# matrix.net
KiCad netlist of a schematic drawn in Altium Designer
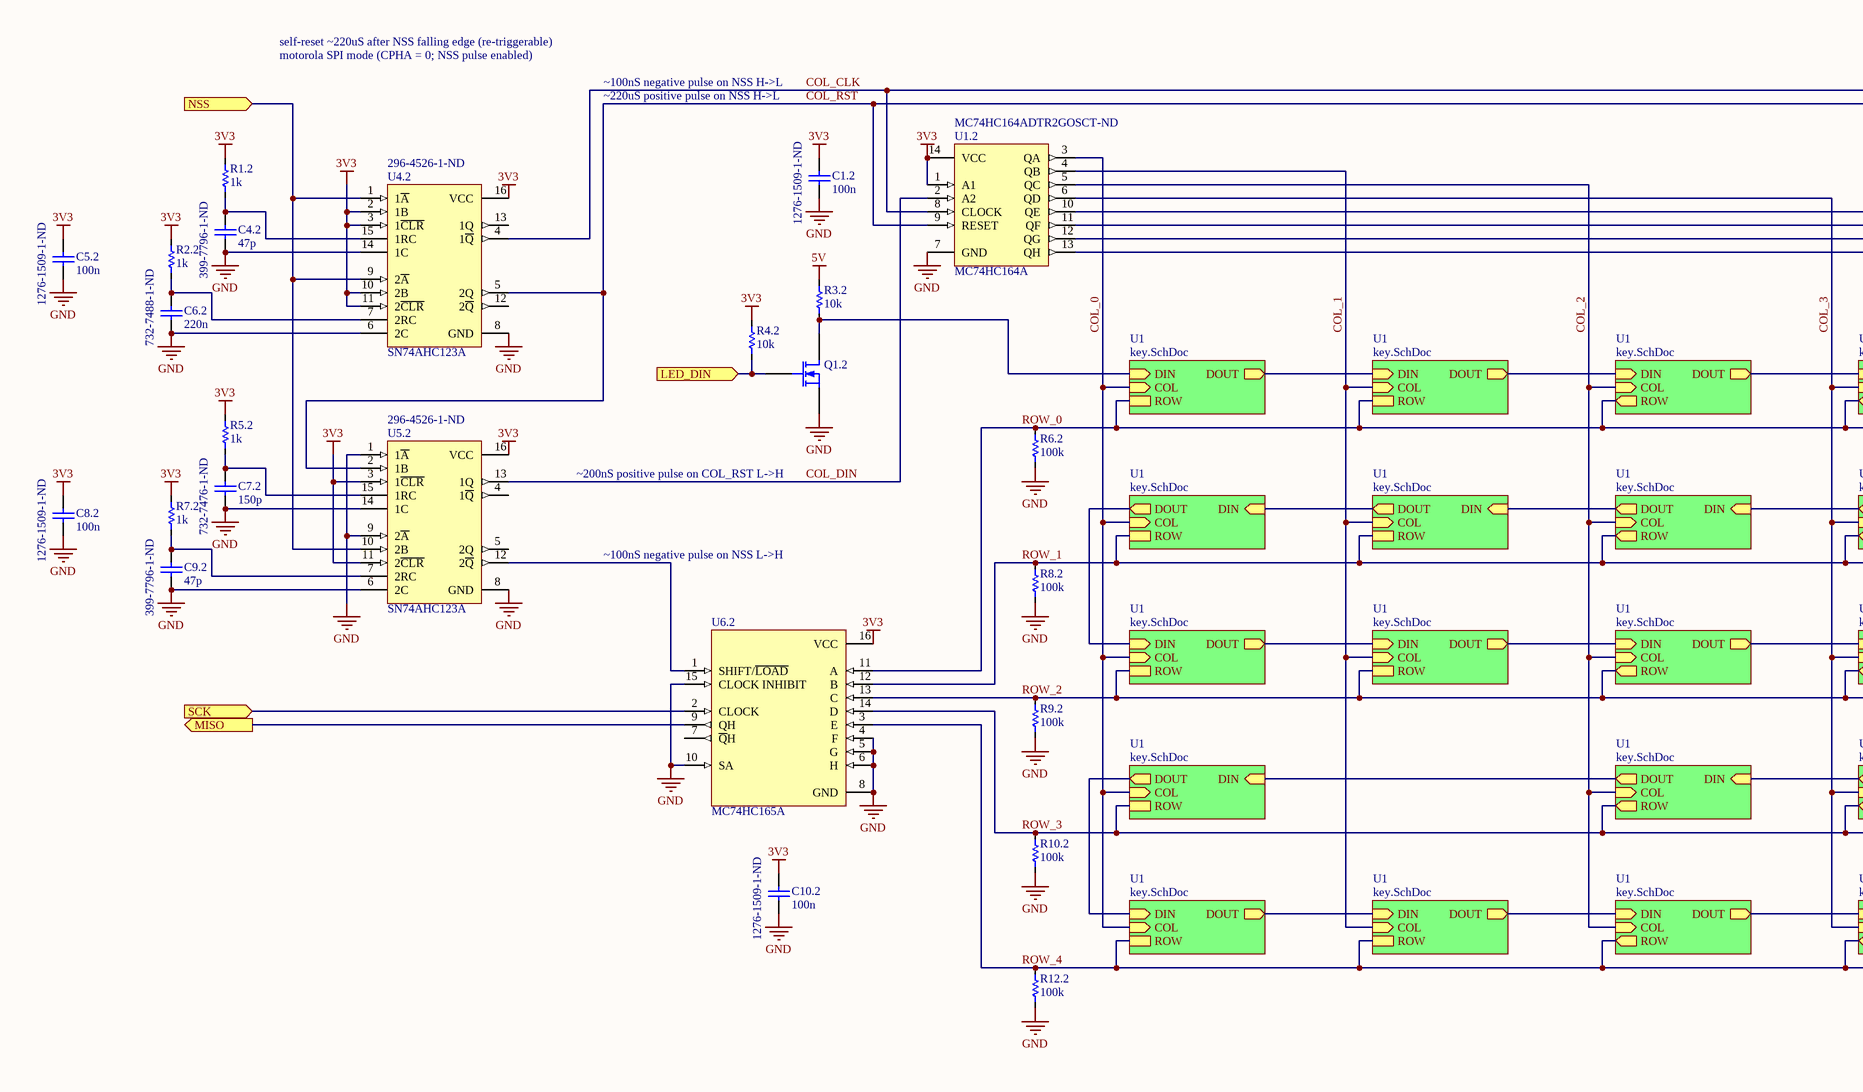
[diagram p0: matrix.SchDoc, left]
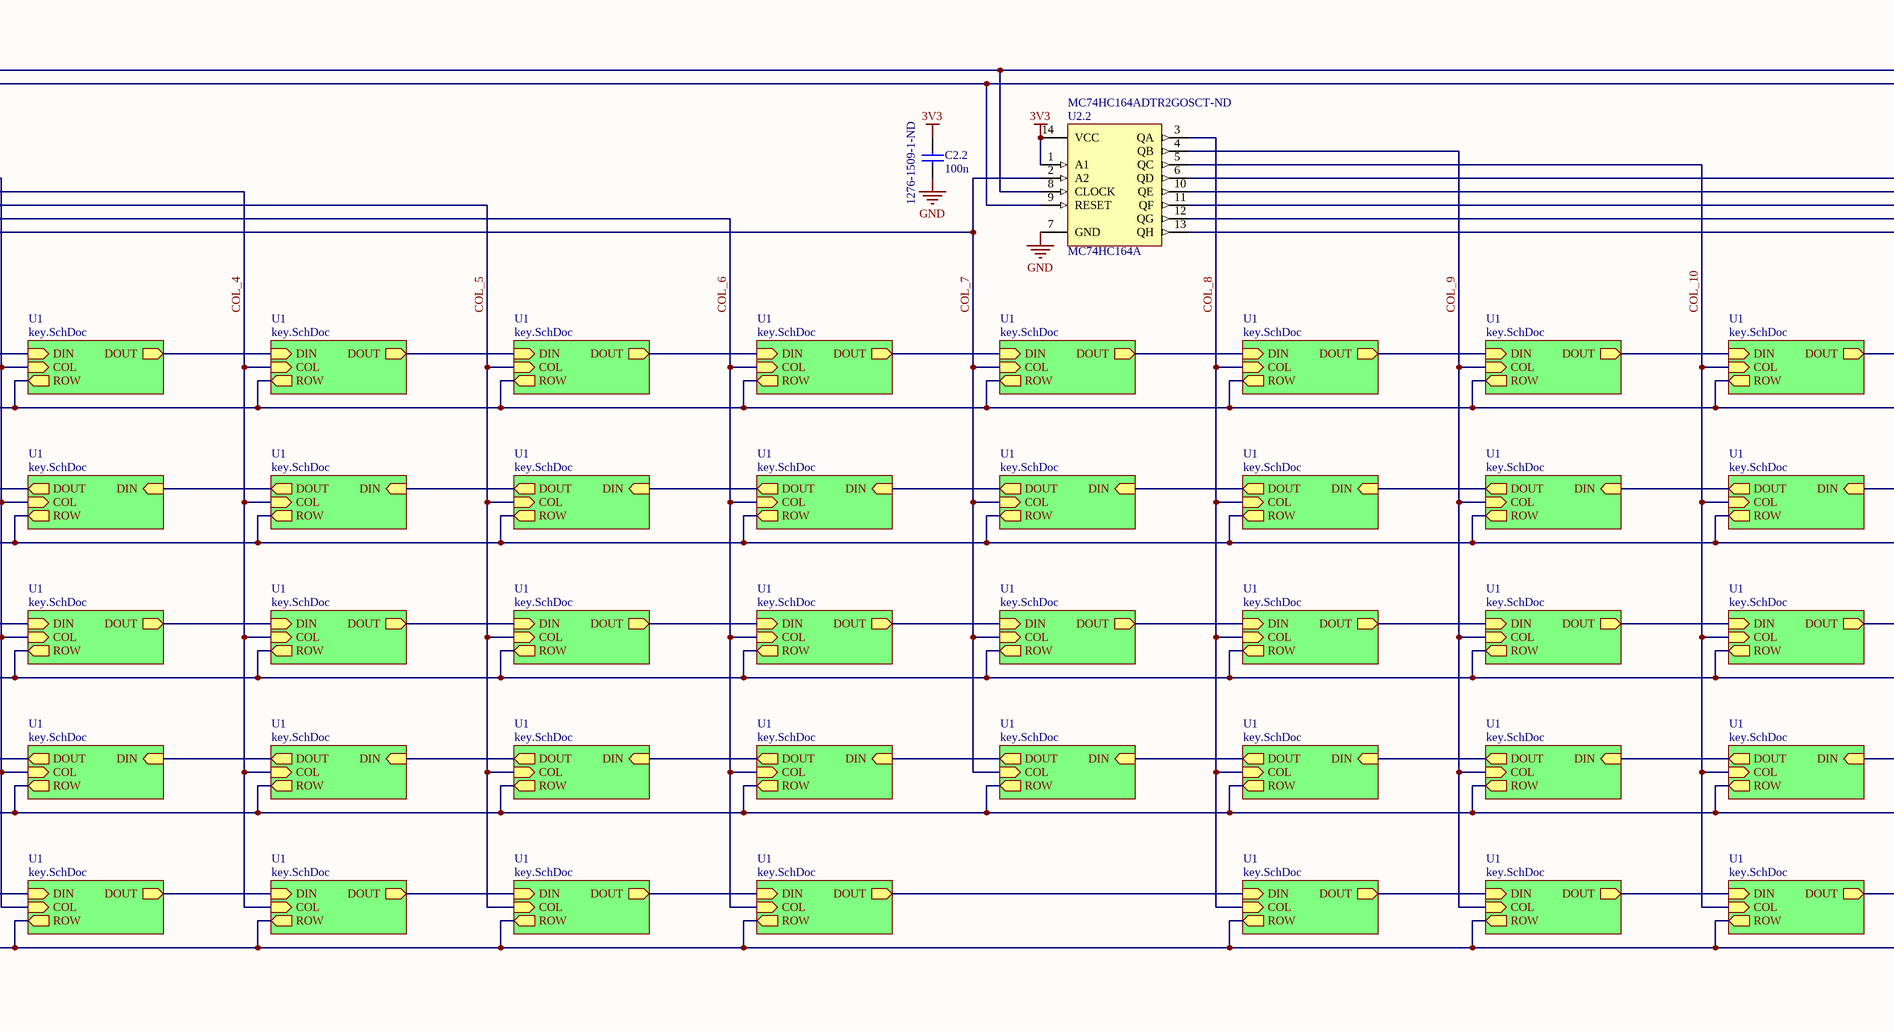
[diagram p1: matrix.SchDoc, middle]
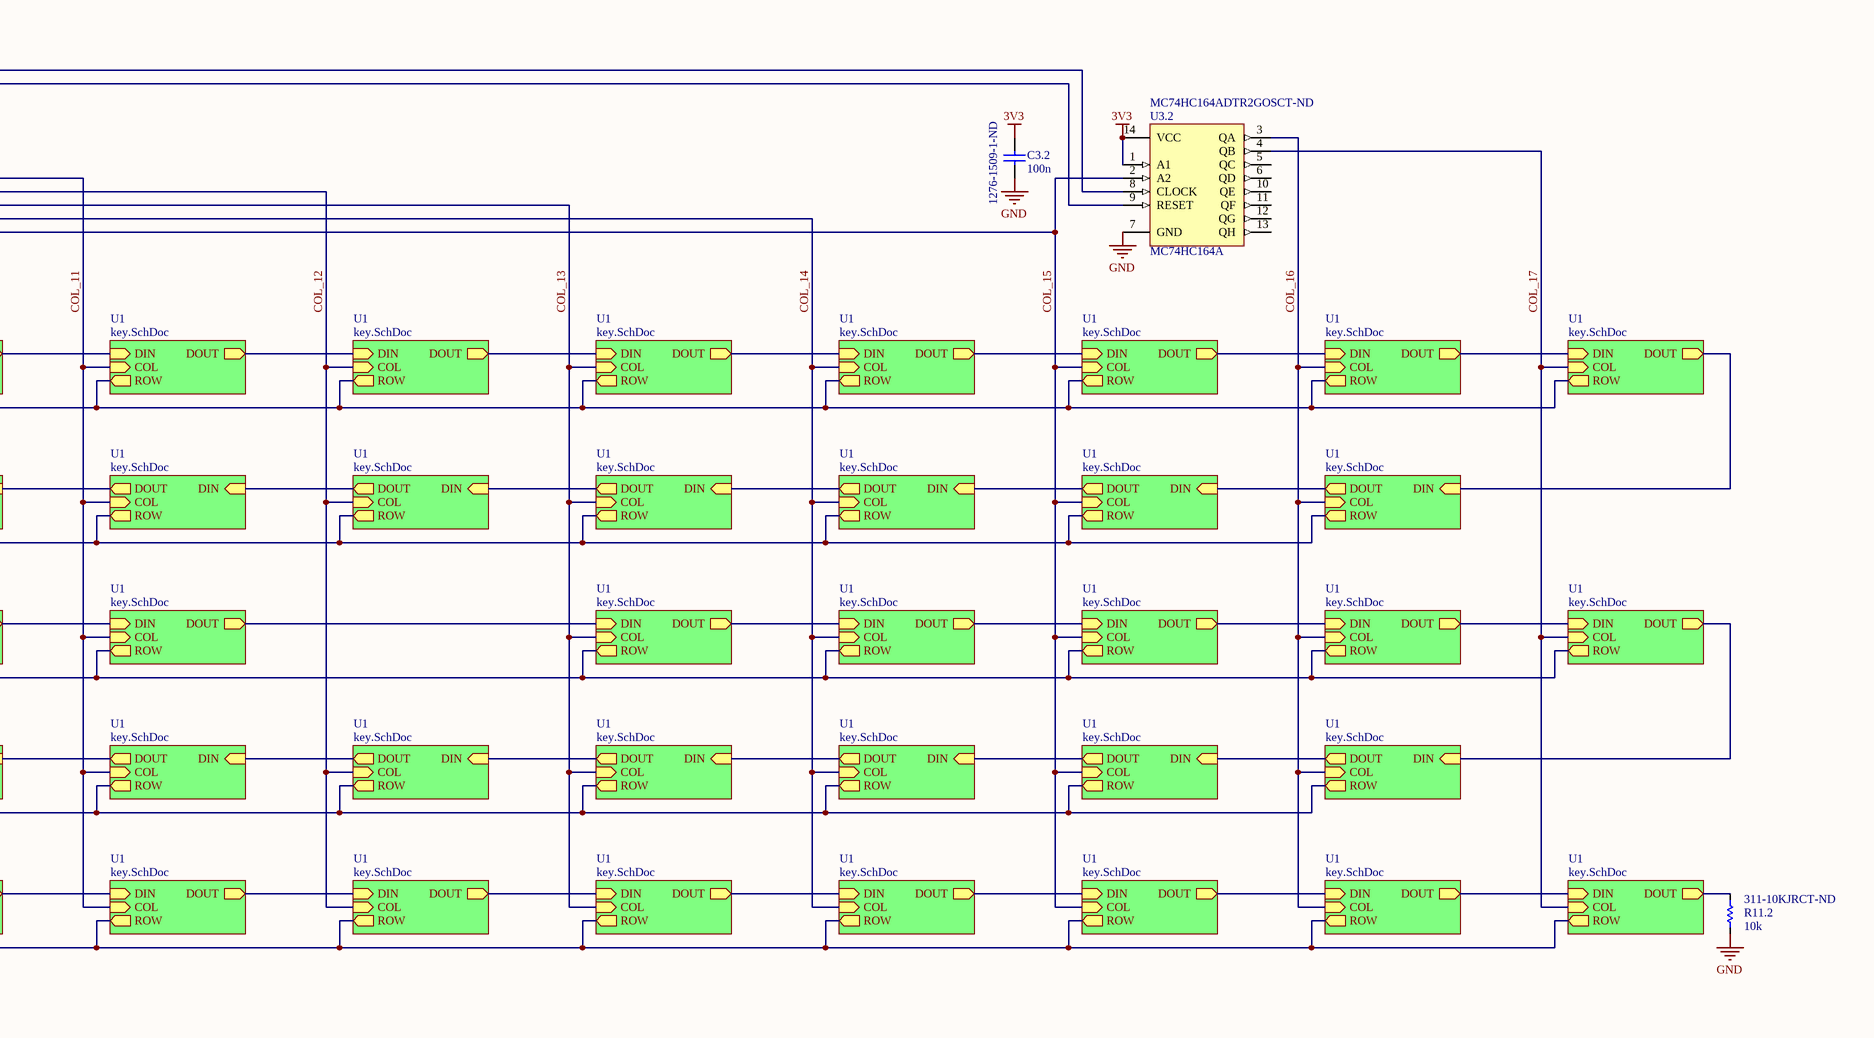
[diagram p2: matrix.SchDoc, right]

(export (version "E")
  (design (tool "Eeschema 10.0.6"))
  (components
    (comp (ref "C1.2")
      (value "100n")
      (footprint "0402")
      (fields (field (name "SUPPLIER PART NUMBER 1") "1276-1509-1-ND"))
      (libsource (lib "Luminaire") (part "CAPACITOR NON_POL"))
    )
    (comp (ref "C2.2")
      (value "100n")
      (footprint "0402")
      (fields (field (name "SUPPLIER PART NUMBER 1") "1276-1509-1-ND"))
      (libsource (lib "Luminaire") (part "CAPACITOR NON_POL"))
    )
    (comp (ref "C3.2")
      (value "100n")
      (footprint "0402")
      (fields (field (name "SUPPLIER PART NUMBER 1") "1276-1509-1-ND"))
      (libsource (lib "Luminaire") (part "CAPACITOR NON_POL"))
    )
    (comp (ref "C4.2")
      (value "47p")
      (footprint "0402")
      (fields (field (name "SUPPLIER PART NUMBER 1") "399-7796-1-ND"))
      (libsource (lib "pokey") (part "CAPACITOR NON_POL"))
    )
    (comp (ref "C5.2")
      (value "100n")
      (footprint "0402")
      (fields (field (name "SUPPLIER PART NUMBER 1") "1276-1509-1-ND"))
      (libsource (lib "Luminaire") (part "CAPACITOR NON_POL"))
    )
    (comp (ref "C6.2")
      (value "220n")
      (footprint "0402")
      (fields (field (name "SUPPLIER PART NUMBER 1") "732-7488-1-ND"))
      (libsource (lib "Luminaire") (part "CAPACITOR NON_POL"))
    )
    (comp (ref "C7.2")
      (value "150p")
      (footprint "0402")
      (fields (field (name "SUPPLIER PART NUMBER 1") "732-7476-1-ND"))
      (libsource (lib "pokey") (part "CAPACITOR NON_POL"))
    )
    (comp (ref "C8.2")
      (value "100n")
      (footprint "0402")
      (fields (field (name "SUPPLIER PART NUMBER 1") "1276-1509-1-ND"))
      (libsource (lib "Luminaire") (part "CAPACITOR NON_POL"))
    )
    (comp (ref "C9.2")
      (value "47p")
      (footprint "0402")
      (fields (field (name "SUPPLIER PART NUMBER 1") "399-7796-1-ND"))
      (libsource (lib "pokey") (part "CAPACITOR NON_POL"))
    )
    (comp (ref "C10.2")
      (value "100n")
      (footprint "0402")
      (fields (field (name "SUPPLIER PART NUMBER 1") "1276-1509-1-ND"))
      (libsource (lib "Luminaire") (part "CAPACITOR NON_POL"))
    )
    (comp (ref "Q1.2")
      (value "2N7002")
      (footprint "SOT23")
      (description "N-Channel Enhancement Mode Vertical DMOS FET")
      (libsource (lib "pokey") (part "2N7002"))
    )
    (comp (ref "R1.2") (value "1k") (footprint "0402") (libsource (lib "pokey") (part "RESISTOR")))
    (comp (ref "R2.2") (value "1k") (footprint "0402") (libsource (lib "pokey") (part "RESISTOR")))
    (comp (ref "R3.2") (value "10k") (footprint "0402") (libsource (lib "pokey") (part "RESISTOR")))
    (comp (ref "R4.2") (value "10k") (footprint "0402") (libsource (lib "pokey") (part "RESISTOR")))
    (comp (ref "R5.2") (value "1k") (footprint "0402") (libsource (lib "pokey") (part "RESISTOR")))
    (comp (ref "R6.2") (value "100k") (footprint "0402") (libsource (lib "pokey") (part "RESISTOR")))
    (comp (ref "R7.2") (value "1k") (footprint "0402") (libsource (lib "pokey") (part "RESISTOR")))
    (comp (ref "R8.2") (value "100k") (footprint "0402") (libsource (lib "pokey") (part "RESISTOR")))
    (comp (ref "R9.2") (value "100k") (footprint "0402") (libsource (lib "pokey") (part "RESISTOR")))
    (comp (ref "R10.2") (value "100k") (footprint "0402") (libsource (lib "pokey") (part "RESISTOR")))
    (comp (ref "R11.2")
      (value "10k")
      (footprint "0402")
      (fields (field (name "SUPPLIER PART NUMBER 1") "311-10KJRCT-ND"))
      (libsource (lib "pokey") (part "RESISTOR"))
    )
    (comp (ref "R12.2") (value "100k") (footprint "0402") (libsource (lib "pokey") (part "RESISTOR")))
    (comp (ref "U1.2")
      (value "MC74HC164A")
      (footprint "TSOP65P640X120-14N")
      (description "IC SHIFT REGISTER 8BIT")
      (fields (field (name "SUPPLIER PART NUMBER 1") "MC74HC164ADTR2GOSCT-ND"))
      (libsource (lib "pokey") (part "MC74HC164A"))
    )
    (comp (ref "U2.2")
      (value "MC74HC164A")
      (footprint "TSOP65P640X120-14N")
      (description "IC SHIFT REGISTER 8BIT")
      (fields (field (name "SUPPLIER PART NUMBER 1") "MC74HC164ADTR2GOSCT-ND"))
      (libsource (lib "pokey") (part "MC74HC164A"))
    )
    (comp (ref "U3.2")
      (value "MC74HC164A")
      (footprint "TSOP65P640X120-14N")
      (description "IC SHIFT REGISTER 8BIT")
      (fields (field (name "SUPPLIER PART NUMBER 1") "MC74HC164ADTR2GOSCT-ND"))
      (libsource (lib "pokey") (part "MC74HC164A"))
    )
    (comp (ref "U4.2")
      (value "SN74AHC123A")
      (footprint "TSSOP16_N")
      (description "IC DUAL RETRIG MULTIVIB")
      (fields (field (name "SUPPLIER PART NUMBER 1") "296-4526-1-ND"))
      (libsource (lib "pokey") (part "SN74AHC123A"))
    )
    (comp (ref "U5.2")
      (value "SN74AHC123A")
      (footprint "TSSOP16_N")
      (description "IC DUAL RETRIG MULTIVIB")
      (fields (field (name "SUPPLIER PART NUMBER 1") "296-4526-1-ND"))
      (libsource (lib "pokey") (part "SN74AHC123A"))
    )
    (comp (ref "U6.2")
      (value "MC74HC165A")
      (footprint "TSSOP16_N")
      (description "IC SHIFT REGISTER IN 8BIT")
      (libsource (lib "pokey") (part "MC74HC165A"))
    )
  )
  (nets
    (net (code "1") (name "/COL_0") (class "Default")
      (node (ref "U1.2") (pin "3") (pinfunction "QA_3") (pintype "output"))
    )
    (net (code "2") (name "/COL_1") (class "Default")
      (node (ref "U1.2") (pin "4") (pinfunction "QB_4") (pintype "output"))
    )
    (net (code "3") (name "/COL_2") (class "Default")
      (node (ref "U1.2") (pin "5") (pinfunction "QC_5") (pintype "output"))
    )
    (net (code "4") (name "/COL_3") (class "Default")
      (node (ref "U1.2") (pin "6") (pinfunction "QD_6") (pintype "output"))
    )
    (net (code "5") (name "/COL_4") (class "Default")
      (node (ref "U1.2") (pin "10") (pinfunction "QE_10") (pintype "output"))
    )
    (net (code "6") (name "/COL_5") (class "Default")
      (node (ref "U1.2") (pin "11") (pinfunction "QF_11") (pintype "output"))
    )
    (net (code "7") (name "/COL_6") (class "Default")
      (node (ref "U1.2") (pin "12") (pinfunction "QG_12") (pintype "output"))
    )
    (net (code "8") (name "/COL_7") (class "Default")
      (node (ref "U1.2") (pin "13") (pinfunction "QH_13") (pintype "output"))
      (node (ref "U2.2") (pin "2") (pinfunction "A2_2") (pintype "input"))
    )
    (net (code "9") (name "/COL_8") (class "Default")
      (node (ref "U2.2") (pin "3") (pinfunction "QA_3") (pintype "output"))
    )
    (net (code "10") (name "/COL_9") (class "Default")
      (node (ref "U2.2") (pin "4") (pinfunction "QB_4") (pintype "output"))
    )
    (net (code "11") (name "/COL_10") (class "Default")
      (node (ref "U2.2") (pin "5") (pinfunction "QC_5") (pintype "output"))
    )
    (net (code "12") (name "/COL_11") (class "Default")
      (node (ref "U2.2") (pin "6") (pinfunction "QD_6") (pintype "output"))
    )
    (net (code "13") (name "/COL_12") (class "Default")
      (node (ref "U2.2") (pin "10") (pinfunction "QE_10") (pintype "output"))
    )
    (net (code "14") (name "/COL_13") (class "Default")
      (node (ref "U2.2") (pin "11") (pinfunction "QF_11") (pintype "output"))
    )
    (net (code "15") (name "/COL_14") (class "Default")
      (node (ref "U2.2") (pin "12") (pinfunction "QG_12") (pintype "output"))
    )
    (net (code "16") (name "/COL_15") (class "Default")
      (node (ref "U2.2") (pin "13") (pinfunction "QH_13") (pintype "output"))
      (node (ref "U3.2") (pin "2") (pinfunction "A2_2") (pintype "input"))
    )
    (net (code "17") (name "/COL_16") (class "Default")
      (node (ref "U3.2") (pin "3") (pinfunction "QA_3") (pintype "output"))
    )
    (net (code "18") (name "/COL_17") (class "Default")
      (node (ref "U3.2") (pin "4") (pinfunction "QB_4") (pintype "output"))
    )
    (net (code "19") (name "/COL_CLK") (class "Default")
      (node (ref "U1.2") (pin "8") (pinfunction "CLOCK_8") (pintype "input"))
      (node (ref "U2.2") (pin "8") (pinfunction "CLOCK_8") (pintype "input"))
      (node (ref "U3.2") (pin "8") (pinfunction "CLOCK_8") (pintype "input"))
      (node (ref "U4.2") (pin "4") (pinfunction "1~{Q}_4") (pintype "output"))
    )
    (net (code "20") (name "/COL_DIN") (class "Default")
      (node (ref "U1.2") (pin "2") (pinfunction "A2_2") (pintype "input"))
      (node (ref "U5.2") (pin "13") (pinfunction "1Q_13") (pintype "output"))
    )
    (net (code "21") (name "/COL_RST") (class "Default")
      (node (ref "U1.2") (pin "9") (pinfunction "RESET_9") (pintype "input"))
      (node (ref "U2.2") (pin "9") (pinfunction "RESET_9") (pintype "input"))
      (node (ref "U3.2") (pin "9") (pinfunction "RESET_9") (pintype "input"))
      (node (ref "U4.2") (pin "5") (pinfunction "2Q_5") (pintype "output"))
      (node (ref "U5.2") (pin "2") (pinfunction "1B_2") (pintype "input"))
    )
    (net (code "22") (name "/DIN") (class "Default")
      (node (ref "Q1.2") (pin "1") (pinfunction "D_1") (pintype "passive"))
      (node (ref "R3.2") (pin "1") (pinfunction "1_1") (pintype "passive"))
    )
    (net (code "23") (name "/DOUT") (class "Default")
      (node (ref "R11.2") (pin "2") (pinfunction "2_2") (pintype "passive"))
    )
    (net (code "108") (name "/LED_DIN") (class "Default")
      (node (ref "Q1.2") (pin "3") (pinfunction "G_3") (pintype "passive"))
      (node (ref "R4.2") (pin "1") (pinfunction "1_1") (pintype "passive"))
    )
    (net (code "109") (name "/MISO") (class "Default")
      (node (ref "U6.2") (pin "9") (pinfunction "QH_9") (pintype "output"))
    )
    (net (code "110") (name "/NSS") (class "Default")
      (node (ref "U4.2") (pin "1") (pinfunction "1~{A}_1") (pintype "input"))
      (node (ref "U4.2") (pin "9") (pinfunction "2~{A}_9") (pintype "input"))
      (node (ref "U5.2") (pin "10") (pinfunction "2B_10") (pintype "input"))
    )
    (net (code "111") (name "/ROW_0") (class "Default")
      (node (ref "R6.2") (pin "2") (pinfunction "2_2") (pintype "passive"))
      (node (ref "U6.2") (pin "11") (pinfunction "A_11") (pintype "input"))
    )
    (net (code "112") (name "/ROW_1") (class "Default")
      (node (ref "R8.2") (pin "2") (pinfunction "2_2") (pintype "passive"))
      (node (ref "U6.2") (pin "12") (pinfunction "B_12") (pintype "input"))
    )
    (net (code "113") (name "/ROW_2") (class "Default")
      (node (ref "R9.2") (pin "2") (pinfunction "2_2") (pintype "passive"))
      (node (ref "U6.2") (pin "13") (pinfunction "C_13") (pintype "input"))
    )
    (net (code "114") (name "/ROW_3") (class "Default")
      (node (ref "R10.2") (pin "2") (pinfunction "2_2") (pintype "passive"))
      (node (ref "U6.2") (pin "14") (pinfunction "D_14") (pintype "input"))
    )
    (net (code "115") (name "/ROW_4") (class "Default")
      (node (ref "R12.2") (pin "2") (pinfunction "2_2") (pintype "passive"))
      (node (ref "U6.2") (pin "3") (pinfunction "E_3") (pintype "input"))
    )
    (net (code "116") (name "/SCK") (class "Default")
      (node (ref "U6.2") (pin "2") (pinfunction "CLOCK_2") (pintype "input"))
    )
    (net (code "117") (name "3V3") (class "Default")
      (node (ref "C1.2") (pin "1") (pinfunction "1_1") (pintype "passive"))
      (node (ref "C10.2") (pin "1") (pinfunction "1_1") (pintype "passive"))
      (node (ref "C2.2") (pin "1") (pinfunction "1_1") (pintype "passive"))
      (node (ref "C3.2") (pin "1") (pinfunction "1_1") (pintype "passive"))
      (node (ref "C5.2") (pin "1") (pinfunction "1_1") (pintype "passive"))
      (node (ref "C8.2") (pin "1") (pinfunction "1_1") (pintype "passive"))
      (node (ref "R1.2") (pin "2") (pinfunction "2_2") (pintype "passive"))
      (node (ref "R2.2") (pin "2") (pinfunction "2_2") (pintype "passive"))
      (node (ref "R4.2") (pin "2") (pinfunction "2_2") (pintype "passive"))
      (node (ref "R5.2") (pin "2") (pinfunction "2_2") (pintype "passive"))
      (node (ref "R7.2") (pin "2") (pinfunction "2_2") (pintype "passive"))
      (node (ref "U1.2") (pin "1") (pinfunction "A1_1") (pintype "input"))
      (node (ref "U1.2") (pin "14") (pinfunction "VCC_14") (pintype "power_in"))
      (node (ref "U2.2") (pin "1") (pinfunction "A1_1") (pintype "input"))
      (node (ref "U2.2") (pin "14") (pinfunction "VCC_14") (pintype "power_in"))
      (node (ref "U3.2") (pin "1") (pinfunction "A1_1") (pintype "input"))
      (node (ref "U3.2") (pin "14") (pinfunction "VCC_14") (pintype "power_in"))
      (node (ref "U4.2") (pin "10") (pinfunction "2B_10") (pintype "input"))
      (node (ref "U4.2") (pin "11") (pinfunction "2~{CLR}_11") (pintype "input"))
      (node (ref "U4.2") (pin "16") (pinfunction "VCC_16") (pintype "power_in"))
      (node (ref "U4.2") (pin "2") (pinfunction "1B_2") (pintype "input"))
      (node (ref "U4.2") (pin "3") (pinfunction "1~{CLR}_3") (pintype "input"))
      (node (ref "U5.2") (pin "11") (pinfunction "2~{CLR}_11") (pintype "input"))
      (node (ref "U5.2") (pin "16") (pinfunction "VCC_16") (pintype "power_in"))
      (node (ref "U5.2") (pin "3") (pinfunction "1~{CLR}_3") (pintype "input"))
      (node (ref "U6.2") (pin "16") (pinfunction "VCC_16") (pintype "power_in"))
    )
    (net (code "118") (name "5V") (class "Default")
      (node (ref "R3.2") (pin "2") (pinfunction "2_2") (pintype "passive"))
    )
    (net (code "119") (name "GND") (class "Default")
      (node (ref "C1.2") (pin "2") (pinfunction "2_2") (pintype "passive"))
      (node (ref "C10.2") (pin "2") (pinfunction "2_2") (pintype "passive"))
      (node (ref "C2.2") (pin "2") (pinfunction "2_2") (pintype "passive"))
      (node (ref "C3.2") (pin "2") (pinfunction "2_2") (pintype "passive"))
      (node (ref "C4.2") (pin "1") (pinfunction "1_1") (pintype "passive"))
      (node (ref "C5.2") (pin "2") (pinfunction "2_2") (pintype "passive"))
      (node (ref "C6.2") (pin "2") (pinfunction "2_2") (pintype "passive"))
      (node (ref "C7.2") (pin "1") (pinfunction "1_1") (pintype "passive"))
      (node (ref "C8.2") (pin "2") (pinfunction "2_2") (pintype "passive"))
      (node (ref "C9.2") (pin "1") (pinfunction "1_1") (pintype "passive"))
      (node (ref "Q1.2") (pin "2") (pinfunction "S_2") (pintype "passive"))
      (node (ref "R10.2") (pin "1") (pinfunction "1_1") (pintype "passive"))
      (node (ref "R11.2") (pin "1") (pinfunction "1_1") (pintype "passive"))
      (node (ref "R12.2") (pin "1") (pinfunction "1_1") (pintype "passive"))
      (node (ref "R6.2") (pin "1") (pinfunction "1_1") (pintype "passive"))
      (node (ref "R8.2") (pin "1") (pinfunction "1_1") (pintype "passive"))
      (node (ref "R9.2") (pin "1") (pinfunction "1_1") (pintype "passive"))
      (node (ref "U1.2") (pin "7") (pinfunction "GND_7") (pintype "power_in"))
      (node (ref "U2.2") (pin "7") (pinfunction "GND_7") (pintype "power_in"))
      (node (ref "U3.2") (pin "7") (pinfunction "GND_7") (pintype "power_in"))
      (node (ref "U4.2") (pin "14") (pinfunction "1C_14") (pintype "passive"))
      (node (ref "U4.2") (pin "6") (pinfunction "2C_6") (pintype "passive"))
      (node (ref "U4.2") (pin "8") (pinfunction "GND_8") (pintype "power_in"))
      (node (ref "U5.2") (pin "1") (pinfunction "1~{A}_1") (pintype "input"))
      (node (ref "U5.2") (pin "14") (pinfunction "1C_14") (pintype "passive"))
      (node (ref "U5.2") (pin "6") (pinfunction "2C_6") (pintype "passive"))
      (node (ref "U5.2") (pin "8") (pinfunction "GND_8") (pintype "power_in"))
      (node (ref "U5.2") (pin "9") (pinfunction "2~{A}_9") (pintype "input"))
      (node (ref "U6.2") (pin "10") (pinfunction "SA_10") (pintype "input"))
      (node (ref "U6.2") (pin "15") (pinfunction "CLOCK_INHIBIT_15") (pintype "input"))
      (node (ref "U6.2") (pin "4") (pinfunction "F_4") (pintype "input"))
      (node (ref "U6.2") (pin "5") (pinfunction "G_5") (pintype "input"))
      (node (ref "U6.2") (pin "6") (pinfunction "H_6") (pintype "input"))
      (node (ref "U6.2") (pin "8") (pinfunction "GND_8") (pintype "power_in"))
    )
    (net (code "120") (name "Net-(U4.2-1RC)") (class "Default")
      (node (ref "C4.2") (pin "2") (pinfunction "2_2") (pintype "passive"))
      (node (ref "R1.2") (pin "1") (pinfunction "1_1") (pintype "passive"))
      (node (ref "U4.2") (pin "15") (pinfunction "1RC_15") (pintype "passive"))
    )
    (net (code "121") (name "Net-(U4.2-2RC)") (class "Default")
      (node (ref "C6.2") (pin "1") (pinfunction "1_1") (pintype "passive"))
      (node (ref "R2.2") (pin "1") (pinfunction "1_1") (pintype "passive"))
      (node (ref "U4.2") (pin "7") (pinfunction "2RC_7") (pintype "passive"))
    )
    (net (code "122") (name "Net-(U5.2-1RC)") (class "Default")
      (node (ref "C7.2") (pin "2") (pinfunction "2_2") (pintype "passive"))
      (node (ref "R5.2") (pin "1") (pinfunction "1_1") (pintype "passive"))
      (node (ref "U5.2") (pin "15") (pinfunction "1RC_15") (pintype "passive"))
    )
    (net (code "123") (name "Net-(U5.2-2RC)") (class "Default")
      (node (ref "C9.2") (pin "2") (pinfunction "2_2") (pintype "passive"))
      (node (ref "R7.2") (pin "1") (pinfunction "1_1") (pintype "passive"))
      (node (ref "U5.2") (pin "7") (pinfunction "2RC_7") (pintype "passive"))
    )
    (net (code "124") (name "Net-(U5.2-2~{Q})") (class "Default")
      (node (ref "U5.2") (pin "12") (pinfunction "2~{Q}_12") (pintype "output"))
      (node (ref "U6.2") (pin "1") (pinfunction "SHIFT/~{LOAD}_1") (pintype "input"))
    )
    (net (code "125") (name "unconnected-(U3.2-QC-Pad5)") (class "Default")
      (node (ref "U3.2") (pin "5") (pinfunction "QC_5") (pintype "output"))
    )
    (net (code "126") (name "unconnected-(U3.2-QD-Pad6)") (class "Default")
      (node (ref "U3.2") (pin "6") (pinfunction "QD_6") (pintype "output"))
    )
    (net (code "127") (name "unconnected-(U3.2-QE-Pad10)") (class "Default")
      (node (ref "U3.2") (pin "10") (pinfunction "QE_10") (pintype "output"))
    )
    (net (code "128") (name "unconnected-(U3.2-QF-Pad11)") (class "Default")
      (node (ref "U3.2") (pin "11") (pinfunction "QF_11") (pintype "output"))
    )
    (net (code "129") (name "unconnected-(U3.2-QG-Pad12)") (class "Default")
      (node (ref "U3.2") (pin "12") (pinfunction "QG_12") (pintype "output"))
    )
    (net (code "130") (name "unconnected-(U3.2-QH-Pad13)") (class "Default")
      (node (ref "U3.2") (pin "13") (pinfunction "QH_13") (pintype "output"))
    )
    (net (code "131") (name "unconnected-(U4.2-1Q-Pad13)") (class "Default")
      (node (ref "U4.2") (pin "13") (pinfunction "1Q_13") (pintype "output"))
    )
    (net (code "132") (name "unconnected-(U4.2-2~{Q}-Pad12)") (class "Default")
      (node (ref "U4.2") (pin "12") (pinfunction "2~{Q}_12") (pintype "output"))
    )
    (net (code "133") (name "unconnected-(U5.2-1~{Q}-Pad4)") (class "Default")
      (node (ref "U5.2") (pin "4") (pinfunction "1~{Q}_4") (pintype "output"))
    )
    (net (code "134") (name "unconnected-(U5.2-2Q-Pad5)") (class "Default")
      (node (ref "U5.2") (pin "5") (pinfunction "2Q_5") (pintype "output"))
    )
    (net (code "135") (name "unconnected-(U6.2-~{Q}H-Pad7)") (class "Default")
      (node (ref "U6.2") (pin "7") (pinfunction "~{Q}H_7") (pintype "output"))
    )
  )
)
